# 80_SignalInput.net
KiCad netlist of a schematic drawn in Altium Designer
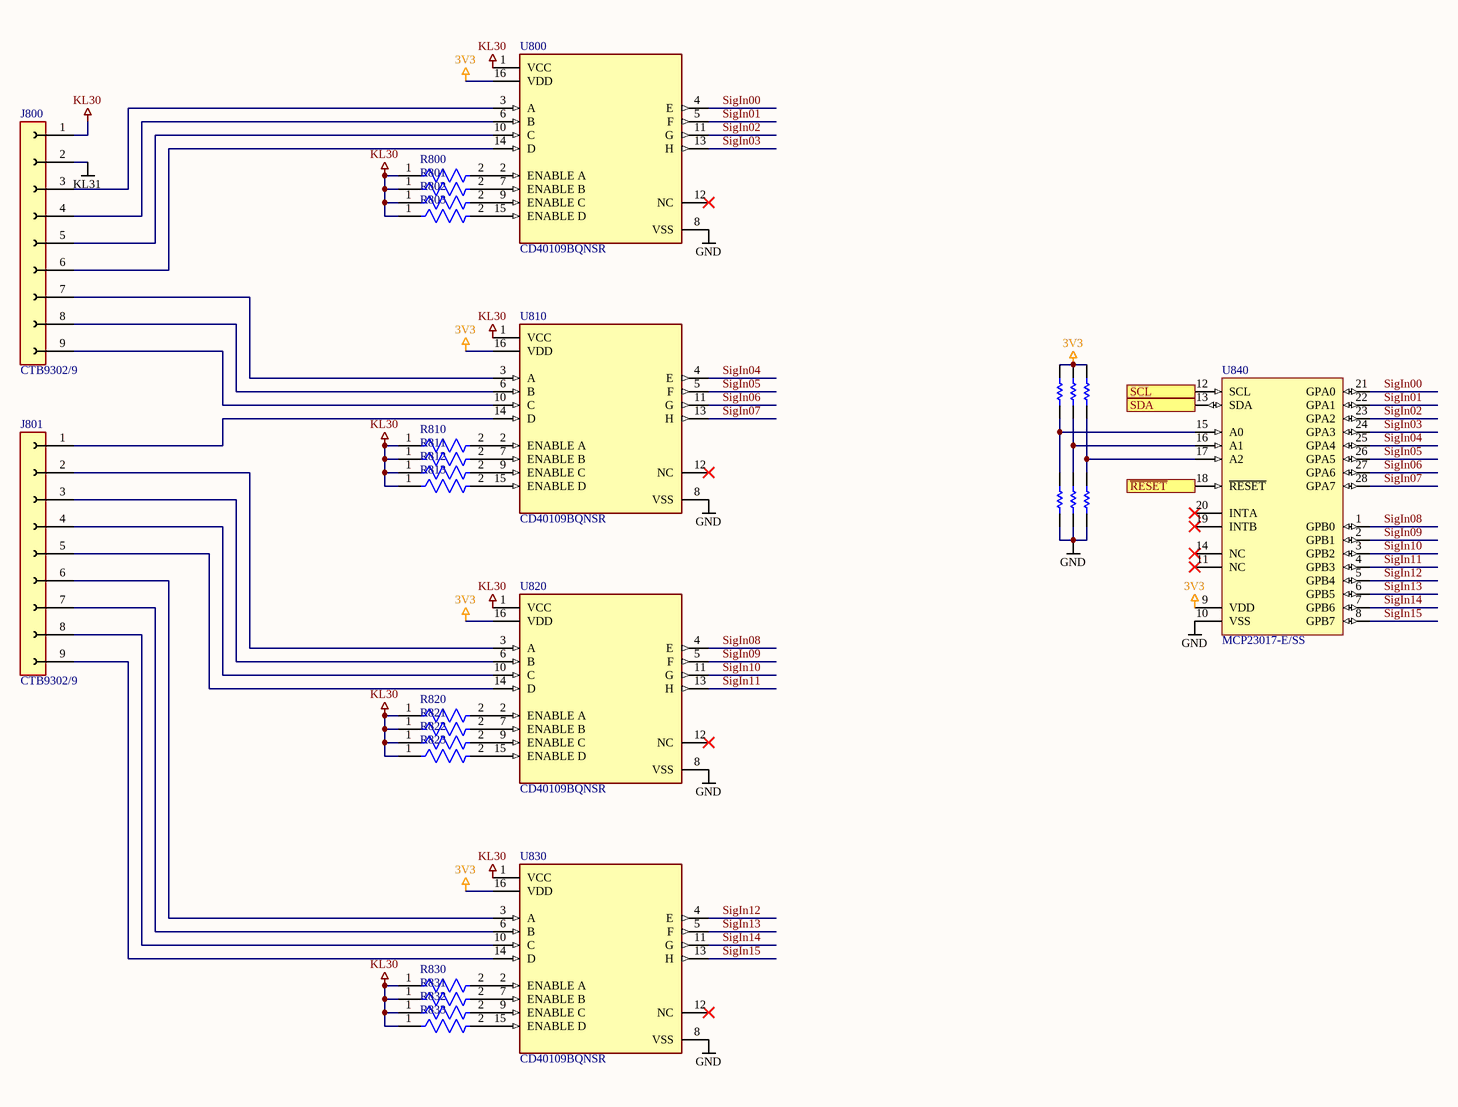
[diagram p0: 80_SignalInput.SchDoc]

(export (version "E")
  (design (tool "Eeschema 10.0.6"))
  (components
    (comp (ref "J800")
      (value "CTB9302/9")
      (footprint "CTB9302-9")
      (description "CTB9302/9 - Stiftleiste - 9-pol, RM 5 mm, 0°")
      (libsource (lib "AltiumLib_MILUTIN") (part "CTB9302-9"))
    )
    (comp (ref "J801")
      (value "CTB9302/9")
      (footprint "CTB9302-9")
      (description "CTB9302/9 - Stiftleiste - 9-pol, RM 5 mm, 0°")
      (libsource (lib "AltiumLib_MILUTIN") (part "CTB9302-9"))
    )
    (comp (ref "R800")
      (value "AC0603FR-071KL")
      (footprint "FP-AC0603-IPC_B")
      (description "RES 1kΩ 1.00% 0.1W 0603")
      (fields (field (name "TOLERANCE") "1%"))
      (libsource (lib "Altium Content Vault") (part "1029c3af85768c4190bb7ad29bc67b5"))
    )
    (comp (ref "R801")
      (value "AC0603FR-071KL")
      (footprint "FP-AC0603-IPC_B")
      (description "RES 1kΩ 1.00% 0.1W 0603")
      (fields (field (name "TOLERANCE") "1%"))
      (libsource (lib "Altium Content Vault") (part "1029c3af85768c4190bb7ad29bc67b5"))
    )
    (comp (ref "R802")
      (value "AC0603FR-071KL")
      (footprint "FP-AC0603-IPC_B")
      (description "RES 1kΩ 1.00% 0.1W 0603")
      (fields (field (name "TOLERANCE") "1%"))
      (libsource (lib "Altium Content Vault") (part "1029c3af85768c4190bb7ad29bc67b5"))
    )
    (comp (ref "R803")
      (value "AC0603FR-071KL")
      (footprint "FP-AC0603-IPC_B")
      (description "RES 1kΩ 1.00% 0.1W 0603")
      (fields (field (name "TOLERANCE") "1%"))
      (libsource (lib "Altium Content Vault") (part "1029c3af85768c4190bb7ad29bc67b5"))
    )
    (comp (ref "R810")
      (value "AC0603FR-071KL")
      (footprint "FP-AC0603-IPC_B")
      (description "RES 1kΩ 1.00% 0.1W 0603")
      (fields (field (name "TOLERANCE") "1%"))
      (libsource (lib "Altium Content Vault") (part "1029c3af85768c4190bb7ad29bc67b5"))
    )
    (comp (ref "R811")
      (value "AC0603FR-071KL")
      (footprint "FP-AC0603-IPC_B")
      (description "RES 1kΩ 1.00% 0.1W 0603")
      (fields (field (name "TOLERANCE") "1%"))
      (libsource (lib "Altium Content Vault") (part "1029c3af85768c4190bb7ad29bc67b5"))
    )
    (comp (ref "R812")
      (value "AC0603FR-071KL")
      (footprint "FP-AC0603-IPC_B")
      (description "RES 1kΩ 1.00% 0.1W 0603")
      (fields (field (name "TOLERANCE") "1%"))
      (libsource (lib "Altium Content Vault") (part "1029c3af85768c4190bb7ad29bc67b5"))
    )
    (comp (ref "R813")
      (value "AC0603FR-071KL")
      (footprint "FP-AC0603-IPC_B")
      (description "RES 1kΩ 1.00% 0.1W 0603")
      (fields (field (name "TOLERANCE") "1%"))
      (libsource (lib "Altium Content Vault") (part "1029c3af85768c4190bb7ad29bc67b5"))
    )
    (comp (ref "R820")
      (value "AC0603FR-071KL")
      (footprint "FP-AC0603-IPC_B")
      (description "RES 1kΩ 1.00% 0.1W 0603")
      (fields (field (name "TOLERANCE") "1%"))
      (libsource (lib "Altium Content Vault") (part "1029c3af85768c4190bb7ad29bc67b5"))
    )
    (comp (ref "R821")
      (value "AC0603FR-071KL")
      (footprint "FP-AC0603-IPC_B")
      (description "RES 1kΩ 1.00% 0.1W 0603")
      (fields (field (name "TOLERANCE") "1%"))
      (libsource (lib "Altium Content Vault") (part "1029c3af85768c4190bb7ad29bc67b5"))
    )
    (comp (ref "R822")
      (value "AC0603FR-071KL")
      (footprint "FP-AC0603-IPC_B")
      (description "RES 1kΩ 1.00% 0.1W 0603")
      (fields (field (name "TOLERANCE") "1%"))
      (libsource (lib "Altium Content Vault") (part "1029c3af85768c4190bb7ad29bc67b5"))
    )
    (comp (ref "R823")
      (value "AC0603FR-071KL")
      (footprint "FP-AC0603-IPC_B")
      (description "RES 1kΩ 1.00% 0.1W 0603")
      (fields (field (name "TOLERANCE") "1%"))
      (libsource (lib "Altium Content Vault") (part "1029c3af85768c4190bb7ad29bc67b5"))
    )
    (comp (ref "R830")
      (value "AC0603FR-071KL")
      (footprint "FP-AC0603-IPC_B")
      (description "RES 1kΩ 1.00% 0.1W 0603")
      (fields (field (name "TOLERANCE") "1%"))
      (libsource (lib "Altium Content Vault") (part "1029c3af85768c4190bb7ad29bc67b5"))
    )
    (comp (ref "R831")
      (value "AC0603FR-071KL")
      (footprint "FP-AC0603-IPC_B")
      (description "RES 1kΩ 1.00% 0.1W 0603")
      (fields (field (name "TOLERANCE") "1%"))
      (libsource (lib "Altium Content Vault") (part "1029c3af85768c4190bb7ad29bc67b5"))
    )
    (comp (ref "R832")
      (value "AC0603FR-071KL")
      (footprint "FP-AC0603-IPC_B")
      (description "RES 1kΩ 1.00% 0.1W 0603")
      (fields (field (name "TOLERANCE") "1%"))
      (libsource (lib "Altium Content Vault") (part "1029c3af85768c4190bb7ad29bc67b5"))
    )
    (comp (ref "R833")
      (value "AC0603FR-071KL")
      (footprint "FP-AC0603-IPC_B")
      (description "RES 1kΩ 1.00% 0.1W 0603")
      (fields (field (name "TOLERANCE") "1%"))
      (libsource (lib "Altium Content Vault") (part "1029c3af85768c4190bb7ad29bc67b5"))
    )
    (comp (ref "R840")
      (value "RC0603JR-070RL")
      (footprint "RESC1608X55X25ML10T15")
      (description "Chip Resistor, 0 Ohm, +/- 5%, 0.1 W, -55 to 155 degC, 0603 (1608 Metric), RoHS, Tape and Reel")
      (fields (field (name "TOLERANCE") "5%") (field (name "MANUFACTURER") "Yageo"))
      (libsource (lib "Altium Content Vault") (part "RES-2"))
    )
    (comp (ref "R841")
      (value "RC0603JR-070RL")
      (footprint "RESC1608X55X25ML10T15")
      (description "Chip Resistor, 0 Ohm, +/- 5%, 0.1 W, -55 to 155 degC, 0603 (1608 Metric), RoHS, Tape and Reel")
      (fields (field (name "TOLERANCE") "5%") (field (name "MANUFACTURER") "Yageo"))
      (libsource (lib "Altium Content Vault") (part "RES-2"))
    )
    (comp (ref "R842")
      (value "RC0603JR-070RL")
      (footprint "RESC1608X55X25ML10T15")
      (description "Chip Resistor, 0 Ohm, +/- 5%, 0.1 W, -55 to 155 degC, 0603 (1608 Metric), RoHS, Tape and Reel")
      (fields (field (name "TOLERANCE") "5%") (field (name "MANUFACTURER") "Yageo"))
      (libsource (lib "Altium Content Vault") (part "RES-2"))
    )
    (comp (ref "R843")
      (value "RC0603JR-070RL")
      (footprint "RESC1608X55X25ML10T15")
      (description "Chip Resistor, 0 Ohm, +/- 5%, 0.1 W, -55 to 155 degC, 0603 (1608 Metric), RoHS, Tape and Reel")
      (fields (field (name "TOLERANCE") "5%") (field (name "MANUFACTURER") "Yageo"))
      (libsource (lib "Altium Content Vault") (part "RES-2"))
    )
    (comp (ref "R844")
      (value "RC0603JR-070RL")
      (footprint "RESC1608X55X25ML10T15")
      (description "Chip Resistor, 0 Ohm, +/- 5%, 0.1 W, -55 to 155 degC, 0603 (1608 Metric), RoHS, Tape and Reel")
      (fields (field (name "TOLERANCE") "5%") (field (name "MANUFACTURER") "Yageo"))
      (libsource (lib "Altium Content Vault") (part "RES-2"))
    )
    (comp (ref "R845")
      (value "RC0603JR-070RL")
      (footprint "RESC1608X55X25ML10T15")
      (description "Chip Resistor, 0 Ohm, +/- 5%, 0.1 W, -55 to 155 degC, 0603 (1608 Metric), RoHS, Tape and Reel")
      (fields (field (name "TOLERANCE") "5%") (field (name "MANUFACTURER") "Yageo"))
      (libsource (lib "Altium Content Vault") (part "RES-2"))
    )
    (comp (ref "U800")
      (value "CD40109BQNSR")
      (footprint "FP-NS0016A-IPC_C")
      (description "IC TRNSLTR UNIDIRECTIONAL 16SO")
      (libsource (lib "Altium Content Vault") (part "478688682dd803327ab49bead7bebe6"))
    )
    (comp (ref "U810")
      (value "CD40109BQNSR")
      (footprint "FP-NS0016A-IPC_C")
      (description "IC TRNSLTR UNIDIRECTIONAL 16SO")
      (libsource (lib "Altium Content Vault") (part "478688682dd803327ab49bead7bebe6"))
    )
    (comp (ref "U820")
      (value "CD40109BQNSR")
      (footprint "FP-NS0016A-IPC_C")
      (description "IC TRNSLTR UNIDIRECTIONAL 16SO")
      (libsource (lib "Altium Content Vault") (part "478688682dd803327ab49bead7bebe6"))
    )
    (comp (ref "U830")
      (value "CD40109BQNSR")
      (footprint "FP-NS0016A-IPC_C")
      (description "IC TRNSLTR UNIDIRECTIONAL 16SO")
      (libsource (lib "Altium Content Vault") (part "478688682dd803327ab49bead7bebe6"))
    )
    (comp (ref "U840")
      (value "MCP23017-E/SS")
      (footprint "SSOP-SS28_N")
      (description "16-Bit I/O Expander with Serial Interface, 28-Pin SSOP, Extended Temperature")
      (libsource (lib "Altium Content Vault") (part "PR-BUSIC-MCP23017-28"))
    )
  )
  (nets
    (net (code "1") (name "/SCL") (class "Default")
      (node (ref "U840") (pin "12") (pinfunction "SCL_12") (pintype "input"))
    )
    (net (code "2") (name "/SDA") (class "Default")
      (node (ref "U840") (pin "13") (pinfunction "SDA_13") (pintype "bidirectional"))
    )
    (net (code "3") (name "/SigIn00") (class "Default")
      (node (ref "U800") (pin "4") (pinfunction "E_4") (pintype "output"))
      (node (ref "U840") (pin "21") (pinfunction "GPA0_21") (pintype "bidirectional"))
    )
    (net (code "4") (name "/SigIn01") (class "Default")
      (node (ref "U800") (pin "5") (pinfunction "F_5") (pintype "output"))
      (node (ref "U840") (pin "22") (pinfunction "GPA1_22") (pintype "bidirectional"))
    )
    (net (code "5") (name "/SigIn02") (class "Default")
      (node (ref "U800") (pin "11") (pinfunction "G_11") (pintype "output"))
      (node (ref "U840") (pin "23") (pinfunction "GPA2_23") (pintype "bidirectional"))
    )
    (net (code "6") (name "/SigIn03") (class "Default")
      (node (ref "U800") (pin "13") (pinfunction "H_13") (pintype "output"))
      (node (ref "U840") (pin "24") (pinfunction "GPA3_24") (pintype "bidirectional"))
    )
    (net (code "7") (name "/SigIn04") (class "Default")
      (node (ref "U810") (pin "4") (pinfunction "E_4") (pintype "output"))
      (node (ref "U840") (pin "25") (pinfunction "GPA4_25") (pintype "bidirectional"))
    )
    (net (code "8") (name "/SigIn05") (class "Default")
      (node (ref "U810") (pin "5") (pinfunction "F_5") (pintype "output"))
      (node (ref "U840") (pin "26") (pinfunction "GPA5_26") (pintype "bidirectional"))
    )
    (net (code "9") (name "/SigIn06") (class "Default")
      (node (ref "U810") (pin "11") (pinfunction "G_11") (pintype "output"))
      (node (ref "U840") (pin "27") (pinfunction "GPA6_27") (pintype "bidirectional"))
    )
    (net (code "10") (name "/SigIn07") (class "Default")
      (node (ref "U810") (pin "13") (pinfunction "H_13") (pintype "output"))
      (node (ref "U840") (pin "28") (pinfunction "GPA7_28") (pintype "bidirectional"))
    )
    (net (code "11") (name "/SigIn08") (class "Default")
      (node (ref "U820") (pin "4") (pinfunction "E_4") (pintype "output"))
      (node (ref "U840") (pin "1") (pinfunction "GPB0_1") (pintype "bidirectional"))
    )
    (net (code "12") (name "/SigIn09") (class "Default")
      (node (ref "U820") (pin "5") (pinfunction "F_5") (pintype "output"))
      (node (ref "U840") (pin "2") (pinfunction "GPB1_2") (pintype "bidirectional"))
    )
    (net (code "13") (name "/SigIn10") (class "Default")
      (node (ref "U820") (pin "11") (pinfunction "G_11") (pintype "output"))
      (node (ref "U840") (pin "3") (pinfunction "GPB2_3") (pintype "bidirectional"))
    )
    (net (code "14") (name "/SigIn11") (class "Default")
      (node (ref "U820") (pin "13") (pinfunction "H_13") (pintype "output"))
      (node (ref "U840") (pin "4") (pinfunction "GPB3_4") (pintype "bidirectional"))
    )
    (net (code "15") (name "/SigIn12") (class "Default")
      (node (ref "U830") (pin "4") (pinfunction "E_4") (pintype "output"))
      (node (ref "U840") (pin "5") (pinfunction "GPB4_5") (pintype "bidirectional"))
    )
    (net (code "16") (name "/SigIn13") (class "Default")
      (node (ref "U830") (pin "5") (pinfunction "F_5") (pintype "output"))
      (node (ref "U840") (pin "6") (pinfunction "GPB5_6") (pintype "bidirectional"))
    )
    (net (code "17") (name "/SigIn14") (class "Default")
      (node (ref "U830") (pin "11") (pinfunction "G_11") (pintype "output"))
      (node (ref "U840") (pin "7") (pinfunction "GPB6_7") (pintype "bidirectional"))
    )
    (net (code "18") (name "/SigIn15") (class "Default")
      (node (ref "U830") (pin "13") (pinfunction "H_13") (pintype "output"))
      (node (ref "U840") (pin "8") (pinfunction "GPB7_8") (pintype "bidirectional"))
    )
    (net (code "19") (name "/~{RESET}") (class "Default")
      (node (ref "U840") (pin "18") (pinfunction "~{RESET}_18") (pintype "input"))
    )
    (net (code "20") (name "3V3") (class "Default")
      (node (ref "R840") (pin "2") (pinfunction "2_2") (pintype "passive"))
      (node (ref "R841") (pin "2") (pinfunction "2_2") (pintype "passive"))
      (node (ref "R842") (pin "2") (pinfunction "2_2") (pintype "passive"))
      (node (ref "U800") (pin "16") (pinfunction "VDD_16") (pintype "power_in"))
      (node (ref "U810") (pin "16") (pinfunction "VDD_16") (pintype "power_in"))
      (node (ref "U820") (pin "16") (pinfunction "VDD_16") (pintype "power_in"))
      (node (ref "U830") (pin "16") (pinfunction "VDD_16") (pintype "power_in"))
      (node (ref "U840") (pin "9") (pinfunction "VDD_9") (pintype "power_in"))
    )
    (net (code "21") (name "GND") (class "Default")
      (node (ref "R843") (pin "1") (pinfunction "1_1") (pintype "passive"))
      (node (ref "R844") (pin "1") (pinfunction "1_1") (pintype "passive"))
      (node (ref "R845") (pin "1") (pinfunction "1_1") (pintype "passive"))
      (node (ref "U800") (pin "8") (pinfunction "VSS_8") (pintype "power_in"))
      (node (ref "U810") (pin "8") (pinfunction "VSS_8") (pintype "power_in"))
      (node (ref "U820") (pin "8") (pinfunction "VSS_8") (pintype "power_in"))
      (node (ref "U830") (pin "8") (pinfunction "VSS_8") (pintype "power_in"))
      (node (ref "U840") (pin "10") (pinfunction "VSS_10") (pintype "power_in"))
    )
    (net (code "22") (name "KL30") (class "Default")
      (node (ref "J800") (pin "1") (pinfunction "1_1") (pintype "power_in"))
      (node (ref "R800") (pin "1") (pinfunction "1_1") (pintype "passive"))
      (node (ref "R801") (pin "1") (pinfunction "1_1") (pintype "passive"))
      (node (ref "R802") (pin "1") (pinfunction "1_1") (pintype "passive"))
      (node (ref "R803") (pin "1") (pinfunction "1_1") (pintype "passive"))
      (node (ref "R810") (pin "1") (pinfunction "1_1") (pintype "passive"))
      (node (ref "R811") (pin "1") (pinfunction "1_1") (pintype "passive"))
      (node (ref "R812") (pin "1") (pinfunction "1_1") (pintype "passive"))
      (node (ref "R813") (pin "1") (pinfunction "1_1") (pintype "passive"))
      (node (ref "R820") (pin "1") (pinfunction "1_1") (pintype "passive"))
      (node (ref "R821") (pin "1") (pinfunction "1_1") (pintype "passive"))
      (node (ref "R822") (pin "1") (pinfunction "1_1") (pintype "passive"))
      (node (ref "R823") (pin "1") (pinfunction "1_1") (pintype "passive"))
      (node (ref "R830") (pin "1") (pinfunction "1_1") (pintype "passive"))
      (node (ref "R831") (pin "1") (pinfunction "1_1") (pintype "passive"))
      (node (ref "R832") (pin "1") (pinfunction "1_1") (pintype "passive"))
      (node (ref "R833") (pin "1") (pinfunction "1_1") (pintype "passive"))
      (node (ref "U800") (pin "1") (pinfunction "VCC_1") (pintype "power_in"))
      (node (ref "U810") (pin "1") (pinfunction "VCC_1") (pintype "power_in"))
      (node (ref "U820") (pin "1") (pinfunction "VCC_1") (pintype "power_in"))
      (node (ref "U830") (pin "1") (pinfunction "VCC_1") (pintype "power_in"))
    )
    (net (code "23") (name "KL31") (class "Default")
      (node (ref "J800") (pin "2") (pinfunction "2_2") (pintype "power_in"))
    )
    (net (code "24") (name "Net-(U800-A)") (class "Default")
      (node (ref "J800") (pin "3") (pinfunction "3_3") (pintype "power_in"))
      (node (ref "U800") (pin "3") (pinfunction "A_3") (pintype "input"))
    )
    (net (code "25") (name "Net-(U800-B)") (class "Default")
      (node (ref "J800") (pin "4") (pinfunction "4_4") (pintype "power_in"))
      (node (ref "U800") (pin "6") (pinfunction "B_6") (pintype "input"))
    )
    (net (code "26") (name "Net-(U800-C)") (class "Default")
      (node (ref "J800") (pin "5") (pinfunction "5_5") (pintype "power_in"))
      (node (ref "U800") (pin "10") (pinfunction "C_10") (pintype "input"))
    )
    (net (code "27") (name "Net-(U800-D)") (class "Default")
      (node (ref "J800") (pin "6") (pinfunction "6_6") (pintype "power_in"))
      (node (ref "U800") (pin "14") (pinfunction "D_14") (pintype "input"))
    )
    (net (code "28") (name "Net-(U800-ENABLE_A)") (class "Default")
      (node (ref "R800") (pin "2") (pinfunction "2_2") (pintype "passive"))
      (node (ref "U800") (pin "2") (pinfunction "ENABLE_A_2") (pintype "input"))
    )
    (net (code "29") (name "Net-(U800-ENABLE_B)") (class "Default")
      (node (ref "R801") (pin "2") (pinfunction "2_2") (pintype "passive"))
      (node (ref "U800") (pin "7") (pinfunction "ENABLE_B_7") (pintype "input"))
    )
    (net (code "30") (name "Net-(U800-ENABLE_C)") (class "Default")
      (node (ref "R802") (pin "2") (pinfunction "2_2") (pintype "passive"))
      (node (ref "U800") (pin "9") (pinfunction "ENABLE_C_9") (pintype "input"))
    )
    (net (code "31") (name "Net-(U800-ENABLE_D)") (class "Default")
      (node (ref "R803") (pin "2") (pinfunction "2_2") (pintype "passive"))
      (node (ref "U800") (pin "15") (pinfunction "ENABLE_D_15") (pintype "input"))
    )
    (net (code "32") (name "Net-(U810-A)") (class "Default")
      (node (ref "J800") (pin "7") (pinfunction "7_7") (pintype "power_in"))
      (node (ref "U810") (pin "3") (pinfunction "A_3") (pintype "input"))
    )
    (net (code "33") (name "Net-(U810-B)") (class "Default")
      (node (ref "J800") (pin "8") (pinfunction "8_8") (pintype "power_in"))
      (node (ref "U810") (pin "6") (pinfunction "B_6") (pintype "input"))
    )
    (net (code "34") (name "Net-(U810-C)") (class "Default")
      (node (ref "J800") (pin "9") (pinfunction "9_9") (pintype "power_in"))
      (node (ref "U810") (pin "10") (pinfunction "C_10") (pintype "input"))
    )
    (net (code "35") (name "Net-(U810-D)") (class "Default")
      (node (ref "J801") (pin "1") (pinfunction "1_1") (pintype "power_in"))
      (node (ref "U810") (pin "14") (pinfunction "D_14") (pintype "input"))
    )
    (net (code "36") (name "Net-(U810-ENABLE_A)") (class "Default")
      (node (ref "R810") (pin "2") (pinfunction "2_2") (pintype "passive"))
      (node (ref "U810") (pin "2") (pinfunction "ENABLE_A_2") (pintype "input"))
    )
    (net (code "37") (name "Net-(U810-ENABLE_B)") (class "Default")
      (node (ref "R811") (pin "2") (pinfunction "2_2") (pintype "passive"))
      (node (ref "U810") (pin "7") (pinfunction "ENABLE_B_7") (pintype "input"))
    )
    (net (code "38") (name "Net-(U810-ENABLE_C)") (class "Default")
      (node (ref "R812") (pin "2") (pinfunction "2_2") (pintype "passive"))
      (node (ref "U810") (pin "9") (pinfunction "ENABLE_C_9") (pintype "input"))
    )
    (net (code "39") (name "Net-(U810-ENABLE_D)") (class "Default")
      (node (ref "R813") (pin "2") (pinfunction "2_2") (pintype "passive"))
      (node (ref "U810") (pin "15") (pinfunction "ENABLE_D_15") (pintype "input"))
    )
    (net (code "40") (name "Net-(U820-A)") (class "Default")
      (node (ref "J801") (pin "2") (pinfunction "2_2") (pintype "power_in"))
      (node (ref "U820") (pin "3") (pinfunction "A_3") (pintype "input"))
    )
    (net (code "41") (name "Net-(U820-B)") (class "Default")
      (node (ref "J801") (pin "3") (pinfunction "3_3") (pintype "power_in"))
      (node (ref "U820") (pin "6") (pinfunction "B_6") (pintype "input"))
    )
    (net (code "42") (name "Net-(U820-C)") (class "Default")
      (node (ref "J801") (pin "4") (pinfunction "4_4") (pintype "power_in"))
      (node (ref "U820") (pin "10") (pinfunction "C_10") (pintype "input"))
    )
    (net (code "43") (name "Net-(U820-D)") (class "Default")
      (node (ref "J801") (pin "5") (pinfunction "5_5") (pintype "power_in"))
      (node (ref "U820") (pin "14") (pinfunction "D_14") (pintype "input"))
    )
    (net (code "44") (name "Net-(U820-ENABLE_A)") (class "Default")
      (node (ref "R820") (pin "2") (pinfunction "2_2") (pintype "passive"))
      (node (ref "U820") (pin "2") (pinfunction "ENABLE_A_2") (pintype "input"))
    )
    (net (code "45") (name "Net-(U820-ENABLE_B)") (class "Default")
      (node (ref "R821") (pin "2") (pinfunction "2_2") (pintype "passive"))
      (node (ref "U820") (pin "7") (pinfunction "ENABLE_B_7") (pintype "input"))
    )
    (net (code "46") (name "Net-(U820-ENABLE_C)") (class "Default")
      (node (ref "R822") (pin "2") (pinfunction "2_2") (pintype "passive"))
      (node (ref "U820") (pin "9") (pinfunction "ENABLE_C_9") (pintype "input"))
    )
    (net (code "47") (name "Net-(U820-ENABLE_D)") (class "Default")
      (node (ref "R823") (pin "2") (pinfunction "2_2") (pintype "passive"))
      (node (ref "U820") (pin "15") (pinfunction "ENABLE_D_15") (pintype "input"))
    )
    (net (code "48") (name "Net-(U830-A)") (class "Default")
      (node (ref "J801") (pin "6") (pinfunction "6_6") (pintype "power_in"))
      (node (ref "U830") (pin "3") (pinfunction "A_3") (pintype "input"))
    )
    (net (code "49") (name "Net-(U830-B)") (class "Default")
      (node (ref "J801") (pin "7") (pinfunction "7_7") (pintype "power_in"))
      (node (ref "U830") (pin "6") (pinfunction "B_6") (pintype "input"))
    )
    (net (code "50") (name "Net-(U830-C)") (class "Default")
      (node (ref "J801") (pin "8") (pinfunction "8_8") (pintype "power_in"))
      (node (ref "U830") (pin "10") (pinfunction "C_10") (pintype "input"))
    )
    (net (code "51") (name "Net-(U830-D)") (class "Default")
      (node (ref "J801") (pin "9") (pinfunction "9_9") (pintype "power_in"))
      (node (ref "U830") (pin "14") (pinfunction "D_14") (pintype "input"))
    )
    (net (code "52") (name "Net-(U830-ENABLE_A)") (class "Default")
      (node (ref "R830") (pin "2") (pinfunction "2_2") (pintype "passive"))
      (node (ref "U830") (pin "2") (pinfunction "ENABLE_A_2") (pintype "input"))
    )
    (net (code "53") (name "Net-(U830-ENABLE_B)") (class "Default")
      (node (ref "R831") (pin "2") (pinfunction "2_2") (pintype "passive"))
      (node (ref "U830") (pin "7") (pinfunction "ENABLE_B_7") (pintype "input"))
    )
    (net (code "54") (name "Net-(U830-ENABLE_C)") (class "Default")
      (node (ref "R832") (pin "2") (pinfunction "2_2") (pintype "passive"))
      (node (ref "U830") (pin "9") (pinfunction "ENABLE_C_9") (pintype "input"))
    )
    (net (code "55") (name "Net-(U830-ENABLE_D)") (class "Default")
      (node (ref "R833") (pin "2") (pinfunction "2_2") (pintype "passive"))
      (node (ref "U830") (pin "15") (pinfunction "ENABLE_D_15") (pintype "input"))
    )
    (net (code "56") (name "Net-(U840-A0)") (class "Default")
      (node (ref "R840") (pin "1") (pinfunction "1_1") (pintype "passive"))
      (node (ref "R843") (pin "2") (pinfunction "2_2") (pintype "passive"))
      (node (ref "U840") (pin "15") (pinfunction "A0_15") (pintype "input"))
    )
    (net (code "57") (name "Net-(U840-A1)") (class "Default")
      (node (ref "R841") (pin "1") (pinfunction "1_1") (pintype "passive"))
      (node (ref "R844") (pin "2") (pinfunction "2_2") (pintype "passive"))
      (node (ref "U840") (pin "16") (pinfunction "A1_16") (pintype "input"))
    )
    (net (code "58") (name "Net-(U840-A2)") (class "Default")
      (node (ref "R842") (pin "1") (pinfunction "1_1") (pintype "passive"))
      (node (ref "R845") (pin "2") (pinfunction "2_2") (pintype "passive"))
      (node (ref "U840") (pin "17") (pinfunction "A2_17") (pintype "input"))
    )
    (net (code "59") (name "unconnected-(U800-NC-Pad12)") (class "Default")
      (node (ref "U800") (pin "12") (pinfunction "NC_12") (pintype "passive+no_connect"))
    )
    (net (code "60") (name "unconnected-(U810-NC-Pad12)") (class "Default")
      (node (ref "U810") (pin "12") (pinfunction "NC_12") (pintype "passive+no_connect"))
    )
    (net (code "61") (name "unconnected-(U820-NC-Pad12)") (class "Default")
      (node (ref "U820") (pin "12") (pinfunction "NC_12") (pintype "passive+no_connect"))
    )
    (net (code "62") (name "unconnected-(U830-NC-Pad12)") (class "Default")
      (node (ref "U830") (pin "12") (pinfunction "NC_12") (pintype "passive+no_connect"))
    )
    (net (code "63") (name "unconnected-(U840-INTA-Pad20)") (class "Default")
      (node (ref "U840") (pin "20") (pinfunction "INTA_20") (pintype "open_collector+no_connect"))
    )
    (net (code "64") (name "unconnected-(U840-INTB-Pad19)") (class "Default")
      (node (ref "U840") (pin "19") (pinfunction "INTB_19") (pintype "open_collector+no_connect"))
    )
    (net (code "65") (name "unconnected-(U840-NC-Pad11)") (class "Default")
      (node (ref "U840") (pin "11") (pinfunction "NC_11") (pintype "passive+no_connect"))
    )
    (net (code "66") (name "unconnected-(U840-NC-Pad14)") (class "Default")
      (node (ref "U840") (pin "14") (pinfunction "NC_14") (pintype "passive+no_connect"))
    )
  )
)
